# Sheet.net
KiCad netlist of a schematic drawn in Altium Designer
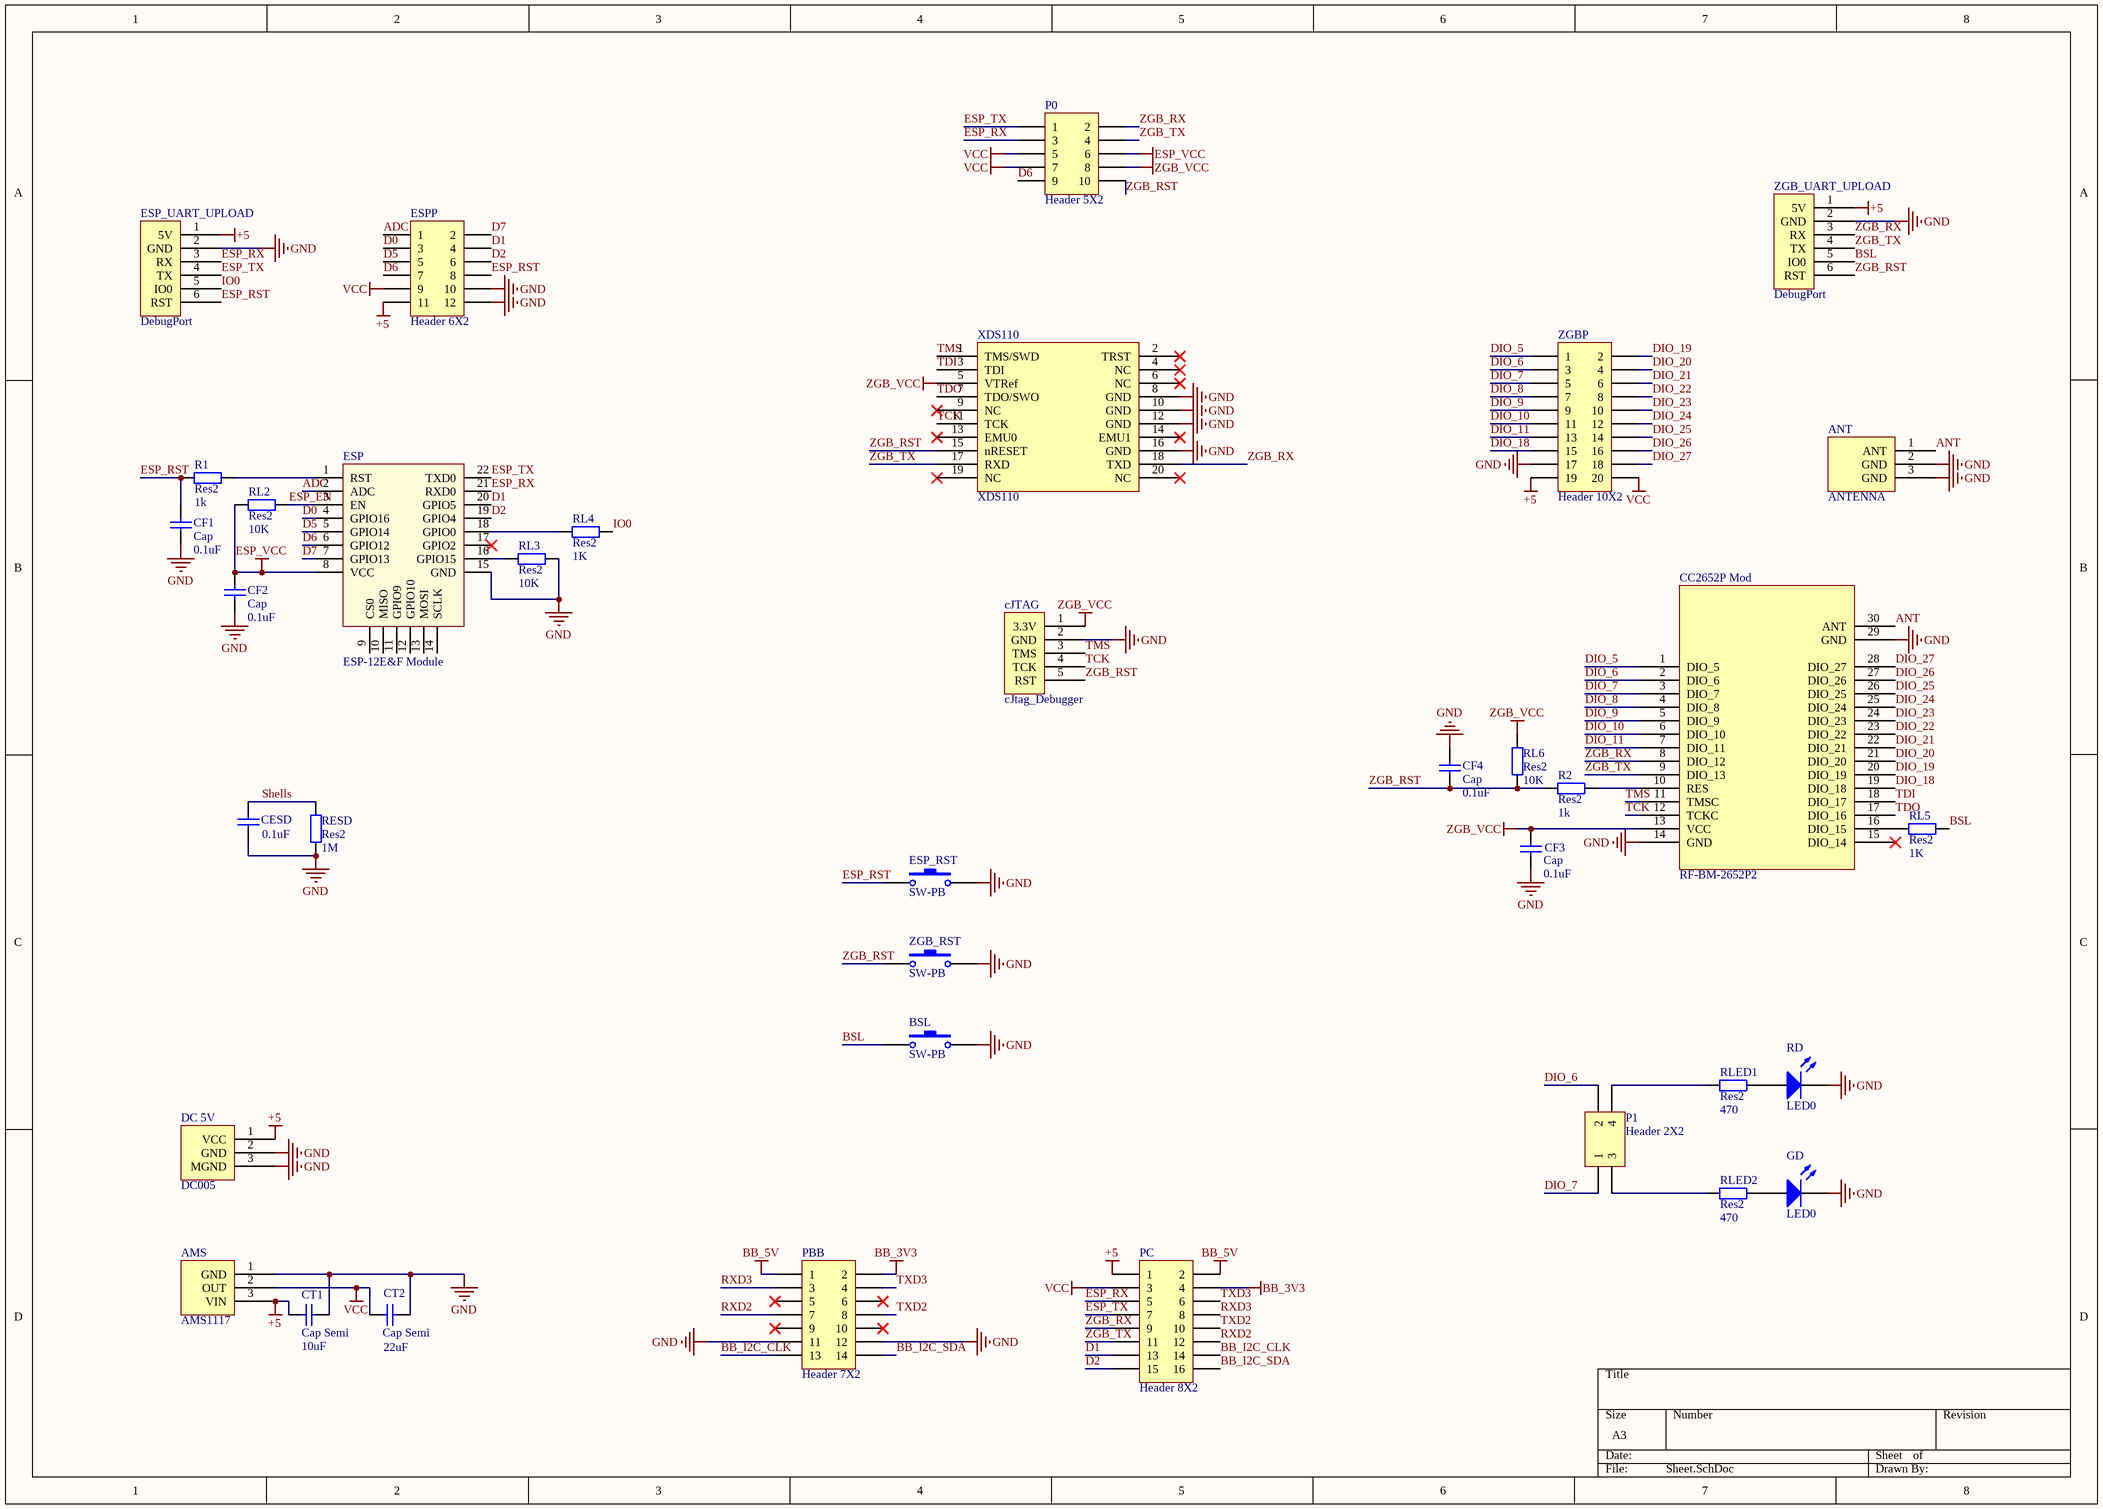
[diagram p0: Sheet.SchDoc]

(export (version "E")
  (design (tool "Eeschema 10.0.6"))
  (components
    (comp (ref "AMS") (value "AMS1117") (footprint "SOT-223-2") (libsource (lib "Schlib2") (part "AMS1117")))
    (comp (ref "ANT") (value "ANTENNA") (footprint "SMA-2") (libsource (lib "我的元件库") (part "ANTENNA")))
    (comp (ref "BSL")
      (value "SW-PB")
      (footprint "TSW SMD-3*6*2.5")
      (description "Switch")
      (fields (field (name "PUBLISHER") "Altium Limited"))
      (libsource (lib "Miscellaneous Devices") (part "SW-PB"))
    )
    (comp (ref "CC2652P Mod")
      (value "RF-BM-2652P2")
      (footprint "RF-BM-2652P2")
      (libsource (lib "我的元件库") (part "RF-BM-2652P2"))
    )
    (comp (ref "CESD")
      (value "0.1uF")
      (footprint "My1206")
      (description "Capacitor")
      (fields (field (name "Comment") "Cap") (field (name "PUBLISHER") "Altium Limited"))
      (libsource (lib "Miscellaneous Devices") (part "Cap"))
    )
    (comp (ref "CF1")
      (value "Cap")
      (footprint "My1206")
      (description "Capacitor")
      (fields (field (name "ALTIUM_VALUE") "0.1uF") (field (name "PUBLISHER") "Altium Limited"))
      (libsource (lib "Miscellaneous Devices") (part "Cap"))
    )
    (comp (ref "CF2")
      (value "Cap")
      (footprint "My1206")
      (description "Capacitor")
      (fields (field (name "ALTIUM_VALUE") "0.1uF") (field (name "PUBLISHER") "Altium Limited"))
      (libsource (lib "Miscellaneous Devices") (part "Cap"))
    )
    (comp (ref "CF3")
      (value "Cap")
      (footprint "My1206")
      (description "Capacitor")
      (fields (field (name "ALTIUM_VALUE") "0.1uF") (field (name "PUBLISHER") "Altium Limited"))
      (libsource (lib "Miscellaneous Devices") (part "Cap"))
    )
    (comp (ref "CF4")
      (value "Cap")
      (footprint "My1206")
      (description "Capacitor")
      (fields (field (name "ALTIUM_VALUE") "0.1uF") (field (name "PUBLISHER") "Altium Limited"))
      (libsource (lib "Miscellaneous Devices") (part "Cap"))
    )
    (comp (ref "cJTAG")
      (value "cJtag_Debugger")
      (footprint "XH2.54-LI-5P")
      (libsource (lib "我的元件库") (part "cJtag_Debugger"))
    )
    (comp (ref "CT1")
      (value "Cap Semi")
      (footprint "My1206")
      (description "Capacitor (Semiconductor SIM Model)")
      (fields (field (name "ALTIUM_VALUE") "10uF") (field (name "PUBLISHER") "Altium Limited"))
      (libsource (lib "Miscellaneous Devices") (part "Cap Semi"))
    )
    (comp (ref "CT2")
      (value "Cap Semi")
      (footprint "My1206")
      (description "Capacitor (Semiconductor SIM Model)")
      (fields (field (name "ALTIUM_VALUE") "22uF") (field (name "PUBLISHER") "Altium Limited"))
      (libsource (lib "Miscellaneous Devices") (part "Cap Semi"))
    )
    (comp (ref "DC 5V") (value "DC005") (footprint "DC-005") (libsource (lib "我的元件库") (part "DC005")))
    (comp (ref "ESP")
      (value "ESP-12E&F Module")
      (footprint "ESP12")
      (libsource (lib "我的元件库") (part "ESP-12E&F Module"))
    )
    (comp (ref "ESPP")
      (value "Header 6X2")
      (footprint "IDC3-6*2")
      (description "Header, 6-Pin, Dual row")
      (fields (field (name "PUBLISHER") "Altium Limited"))
      (libsource (lib "Miscellaneous Connectors") (part "Header 6X2"))
    )
    (comp (ref "ESP_RST")
      (value "SW-PB")
      (footprint "TSW SMD-3*6*2.5")
      (description "Switch")
      (fields (field (name "PUBLISHER") "Altium Limited"))
      (libsource (lib "Miscellaneous Devices") (part "SW-PB"))
    )
    (comp (ref "ESP_UART_UPLOAD")
      (value "DebugPort")
      (footprint "XH2.54-LI-6P")
      (libsource (lib "ESP12_BME280_OLED_IR") (part "DebugPort"))
    )
    (comp (ref "GD")
      (value "LED0")
      (footprint "My1206")
      (description "Typical INFRARED GaAs LED")
      (fields (field (name "PUBLISHER") "Altium Limited"))
      (libsource (lib "Miscellaneous Devices") (part "LED0"))
    )
    (comp (ref "P0")
      (value "Header 5X2")
      (footprint "HDR2X5")
      (description "Header, 5-Pin, Dual row")
      (fields (field (name "PUBLISHER") "Altium Limited"))
      (libsource (lib "Miscellaneous Connectors") (part "Header 5X2"))
    )
    (comp (ref "P1")
      (value "Header 2X2")
      (footprint "HDR2X2")
      (description "Header, 2-Pin, Dual row")
      (fields (field (name "PUBLISHER") "Altium Limited"))
      (libsource (lib "Miscellaneous Connectors") (part "Header 2X2"))
    )
    (comp (ref "PBB")
      (value "Header 7X2")
      (footprint "IDC3-7*2")
      (description "Header, 7-Pin, Dual row")
      (fields (field (name "PUBLISHER") "Altium Limited"))
      (libsource (lib "Miscellaneous Connectors") (part "Header 7X2"))
    )
    (comp (ref "PC")
      (value "Header 8X2")
      (footprint "HDR2X8")
      (description "Header, 8-Pin, Dual row")
      (fields (field (name "PUBLISHER") "Altium Limited"))
      (libsource (lib "Miscellaneous Connectors") (part "Header 8X2"))
    )
    (comp (ref "R1")
      (value "Res2")
      (footprint "My1206")
      (description "Resistor")
      (fields (field (name "ALTIUM_VALUE") "1k") (field (name "PUBLISHER") "Altium Limited"))
      (libsource (lib "Miscellaneous Devices") (part "Res2"))
    )
    (comp (ref "R2")
      (value "Res2")
      (footprint "My1206")
      (description "Resistor")
      (fields (field (name "ALTIUM_VALUE") "1k") (field (name "PUBLISHER") "Altium Limited"))
      (libsource (lib "Miscellaneous Devices") (part "Res2"))
    )
    (comp (ref "RD")
      (value "LED0")
      (footprint "My1206")
      (description "Typical INFRARED GaAs LED")
      (fields (field (name "PUBLISHER") "Altium Limited"))
      (libsource (lib "Miscellaneous Devices") (part "LED0"))
    )
    (comp (ref "RESD")
      (value "Res2")
      (footprint "My1206")
      (description "Resistor")
      (fields (field (name "ALTIUM_VALUE") "1M") (field (name "PUBLISHER") "Altium Limited"))
      (libsource (lib "") (part "Res2_1"))
    )
    (comp (ref "RL2")
      (value "Res2")
      (footprint "My1206")
      (description "Resistor")
      (fields (field (name "ALTIUM_VALUE") "10K") (field (name "PUBLISHER") "Altium Limited"))
      (libsource (lib "Miscellaneous Devices") (part "Res2"))
    )
    (comp (ref "RL3")
      (value "Res2")
      (footprint "My1206")
      (description "Resistor")
      (fields (field (name "ALTIUM_VALUE") "10K") (field (name "PUBLISHER") "Altium Limited"))
      (libsource (lib "Miscellaneous Devices") (part "Res2"))
    )
    (comp (ref "RL4")
      (value "Res2")
      (footprint "My1206")
      (description "Resistor")
      (fields (field (name "ALTIUM_VALUE") "1K") (field (name "PUBLISHER") "Altium Limited"))
      (libsource (lib "Miscellaneous Devices") (part "Res2"))
    )
    (comp (ref "RL5")
      (value "Res2")
      (footprint "My1206")
      (description "Resistor")
      (fields (field (name "ALTIUM_VALUE") "1K") (field (name "PUBLISHER") "Altium Limited"))
      (libsource (lib "Miscellaneous Devices") (part "Res2"))
    )
    (comp (ref "RL6")
      (value "Res2")
      (footprint "My1206")
      (description "Resistor")
      (fields (field (name "ALTIUM_VALUE") "10K") (field (name "PUBLISHER") "Altium Limited"))
      (libsource (lib "") (part "Res2_1"))
    )
    (comp (ref "RLED1")
      (value "Res2")
      (footprint "My1206")
      (description "Resistor")
      (fields (field (name "ALTIUM_VALUE") "470") (field (name "PUBLISHER") "Altium Limited"))
      (libsource (lib "Miscellaneous Devices") (part "Res2"))
    )
    (comp (ref "RLED2")
      (value "Res2")
      (footprint "My1206")
      (description "Resistor")
      (fields (field (name "ALTIUM_VALUE") "470") (field (name "PUBLISHER") "Altium Limited"))
      (libsource (lib "Miscellaneous Devices") (part "Res2"))
    )
    (comp (ref "XDS110") (value "XDS110") (footprint "IDC3-10*2") (libsource (lib "我的元件库") (part "XDS110")))
    (comp (ref "ZGBP")
      (value "Header 10X2")
      (footprint "HDR2X10")
      (description "Header, 10-Pin, Dual row")
      (fields (field (name "PUBLISHER") "Altium Limited"))
      (libsource (lib "Miscellaneous Connectors") (part "Header 10X2"))
    )
    (comp (ref "ZGB_RST")
      (value "SW-PB")
      (footprint "TSW SMD-3*6*2.5")
      (description "Switch")
      (fields (field (name "PUBLISHER") "Altium Limited"))
      (libsource (lib "Miscellaneous Devices") (part "SW-PB"))
    )
    (comp (ref "ZGB_UART_UPLOAD")
      (value "DebugPort")
      (footprint "XH2.54-LI-6P")
      (libsource (lib "ESP12_BME280_OLED_IR") (part "DebugPort"))
    )
  )
  (nets
    (net (code "1") (name "+5") (class "Default")
      (node (ref "AMS") (pin "3") (pinfunction "VIN_3") (pintype "passive"))
      (node (ref "CT1") (pin "1") (pinfunction "1_1") (pintype "passive"))
      (node (ref "DC 5V") (pin "1") (pinfunction "VCC_1") (pintype "passive"))
      (node (ref "ESPP") (pin "11") (pinfunction "11_11") (pintype "passive"))
      (node (ref "ESP_UART_UPLOAD") (pin "1") (pinfunction "5V_1") (pintype "passive"))
      (node (ref "PC") (pin "1") (pinfunction "1_1") (pintype "passive"))
      (node (ref "ZGBP") (pin "19") (pinfunction "19_19") (pintype "passive"))
      (node (ref "ZGB_UART_UPLOAD") (pin "1") (pinfunction "5V_1") (pintype "passive"))
    )
    (net (code "3") (name "/ADC") (class "Default")
      (node (ref "ESP") (pin "2") (pinfunction "ADC_2") (pintype "passive"))
      (node (ref "ESPP") (pin "1") (pinfunction "1_1") (pintype "passive"))
    )
    (net (code "4") (name "/ANT") (class "Default")
      (node (ref "ANT") (pin "1") (pinfunction "ANT_1") (pintype "passive"))
      (node (ref "CC2652P Mod") (pin "30") (pinfunction "ANT_30") (pintype "passive"))
    )
    (net (code "5") (name "/BB_I2C_CLK") (class "Default")
      (node (ref "PBB") (pin "13") (pinfunction "13_13") (pintype "passive"))
      (node (ref "PC") (pin "14") (pinfunction "14_14") (pintype "passive"))
    )
    (net (code "6") (name "/BB_I2C_SDA") (class "Default")
      (node (ref "PBB") (pin "14") (pinfunction "14_14") (pintype "passive"))
      (node (ref "PC") (pin "16") (pinfunction "16_16") (pintype "passive"))
    )
    (net (code "7") (name "/BSL") (class "Default")
      (node (ref "BSL") (pin "1") (pinfunction "1_1") (pintype "passive"))
      (node (ref "RL5") (pin "2") (pinfunction "2_2") (pintype "passive"))
      (node (ref "ZGB_UART_UPLOAD") (pin "5") (pinfunction "IO0_5") (pintype "passive"))
    )
    (net (code "8") (name "/D0") (class "Default")
      (node (ref "ESP") (pin "4") (pinfunction "GPIO16_4") (pintype "passive"))
      (node (ref "ESPP") (pin "3") (pinfunction "3_3") (pintype "passive"))
    )
    (net (code "9") (name "/D1") (class "Default")
      (node (ref "ESP") (pin "20") (pinfunction "GPIO5_20") (pintype "passive"))
      (node (ref "ESPP") (pin "4") (pinfunction "4_4") (pintype "passive"))
      (node (ref "PC") (pin "13") (pinfunction "13_13") (pintype "passive"))
    )
    (net (code "10") (name "/D2") (class "Default")
      (node (ref "ESP") (pin "19") (pinfunction "GPIO4_19") (pintype "passive"))
      (node (ref "ESPP") (pin "6") (pinfunction "6_6") (pintype "passive"))
      (node (ref "PC") (pin "15") (pinfunction "15_15") (pintype "passive"))
    )
    (net (code "11") (name "/D5") (class "Default")
      (node (ref "ESP") (pin "5") (pinfunction "GPIO14_5") (pintype "passive"))
      (node (ref "ESPP") (pin "5") (pinfunction "5_5") (pintype "passive"))
    )
    (net (code "12") (name "/D6") (class "Default")
      (node (ref "ESP") (pin "6") (pinfunction "GPIO12_6") (pintype "passive"))
      (node (ref "ESPP") (pin "7") (pinfunction "7_7") (pintype "passive"))
      (node (ref "P0") (pin "9") (pinfunction "9_9") (pintype "passive"))
    )
    (net (code "13") (name "/D7") (class "Default")
      (node (ref "ESP") (pin "7") (pinfunction "GPIO13_7") (pintype "passive"))
      (node (ref "ESPP") (pin "2") (pinfunction "2_2") (pintype "passive"))
    )
    (net (code "14") (name "/DIO_5") (class "Default")
      (node (ref "CC2652P Mod") (pin "1") (pinfunction "DIO_5_1") (pintype "passive"))
      (node (ref "ZGBP") (pin "1") (pinfunction "1_1") (pintype "passive"))
    )
    (net (code "15") (name "/DIO_6") (class "Default")
      (node (ref "CC2652P Mod") (pin "2") (pinfunction "DIO_6_2") (pintype "passive"))
      (node (ref "P1") (pin "2") (pinfunction "2_2") (pintype "passive"))
      (node (ref "ZGBP") (pin "3") (pinfunction "3_3") (pintype "passive"))
    )
    (net (code "16") (name "/DIO_7") (class "Default")
      (node (ref "CC2652P Mod") (pin "3") (pinfunction "DIO_7_3") (pintype "passive"))
      (node (ref "P1") (pin "1") (pinfunction "1_1") (pintype "passive"))
      (node (ref "ZGBP") (pin "5") (pinfunction "5_5") (pintype "passive"))
    )
    (net (code "17") (name "/DIO_8") (class "Default")
      (node (ref "CC2652P Mod") (pin "4") (pinfunction "DIO_8_4") (pintype "passive"))
      (node (ref "ZGBP") (pin "7") (pinfunction "7_7") (pintype "passive"))
    )
    (net (code "18") (name "/DIO_9") (class "Default")
      (node (ref "CC2652P Mod") (pin "5") (pinfunction "DIO_9_5") (pintype "passive"))
      (node (ref "ZGBP") (pin "9") (pinfunction "9_9") (pintype "passive"))
    )
    (net (code "19") (name "/DIO_10") (class "Default")
      (node (ref "CC2652P Mod") (pin "6") (pinfunction "DIO_10_6") (pintype "passive"))
      (node (ref "ZGBP") (pin "11") (pinfunction "11_11") (pintype "passive"))
    )
    (net (code "20") (name "/DIO_11") (class "Default")
      (node (ref "CC2652P Mod") (pin "7") (pinfunction "DIO_11_7") (pintype "passive"))
      (node (ref "ZGBP") (pin "13") (pinfunction "13_13") (pintype "passive"))
    )
    (net (code "21") (name "/DIO_18") (class "Default")
      (node (ref "CC2652P Mod") (pin "19") (pinfunction "DIO_18_19") (pintype "passive"))
      (node (ref "ZGBP") (pin "15") (pinfunction "15_15") (pintype "passive"))
    )
    (net (code "22") (name "/DIO_19") (class "Default")
      (node (ref "CC2652P Mod") (pin "20") (pinfunction "DIO_19_20") (pintype "passive"))
      (node (ref "ZGBP") (pin "2") (pinfunction "2_2") (pintype "passive"))
    )
    (net (code "23") (name "/DIO_20") (class "Default")
      (node (ref "CC2652P Mod") (pin "21") (pinfunction "DIO_20_21") (pintype "passive"))
      (node (ref "ZGBP") (pin "4") (pinfunction "4_4") (pintype "passive"))
    )
    (net (code "24") (name "/DIO_21") (class "Default")
      (node (ref "CC2652P Mod") (pin "22") (pinfunction "DIO_21_22") (pintype "passive"))
      (node (ref "ZGBP") (pin "6") (pinfunction "6_6") (pintype "passive"))
    )
    (net (code "25") (name "/DIO_22") (class "Default")
      (node (ref "CC2652P Mod") (pin "23") (pinfunction "DIO_22_23") (pintype "passive"))
      (node (ref "ZGBP") (pin "8") (pinfunction "8_8") (pintype "passive"))
    )
    (net (code "26") (name "/DIO_23") (class "Default")
      (node (ref "CC2652P Mod") (pin "24") (pinfunction "DIO_23_24") (pintype "passive"))
      (node (ref "ZGBP") (pin "10") (pinfunction "10_10") (pintype "passive"))
    )
    (net (code "27") (name "/DIO_24") (class "Default")
      (node (ref "CC2652P Mod") (pin "25") (pinfunction "DIO_24_25") (pintype "passive"))
      (node (ref "ZGBP") (pin "12") (pinfunction "12_12") (pintype "passive"))
    )
    (net (code "28") (name "/DIO_25") (class "Default")
      (node (ref "CC2652P Mod") (pin "26") (pinfunction "DIO_25_26") (pintype "passive"))
      (node (ref "ZGBP") (pin "14") (pinfunction "14_14") (pintype "passive"))
    )
    (net (code "29") (name "/DIO_26") (class "Default")
      (node (ref "CC2652P Mod") (pin "27") (pinfunction "DIO_26_27") (pintype "passive"))
      (node (ref "ZGBP") (pin "16") (pinfunction "16_16") (pintype "passive"))
    )
    (net (code "30") (name "/DIO_27") (class "Default")
      (node (ref "CC2652P Mod") (pin "28") (pinfunction "DIO_27_28") (pintype "passive"))
      (node (ref "ZGBP") (pin "18") (pinfunction "18_18") (pintype "passive"))
    )
    (net (code "31") (name "/ESP_EN") (class "Default")
      (node (ref "ESP") (pin "3") (pinfunction "EN_3") (pintype "passive"))
      (node (ref "RL2") (pin "2") (pinfunction "2_2") (pintype "passive"))
    )
    (net (code "32") (name "/ESP_RST") (class "Default")
      (node (ref "CF1") (pin "2") (pinfunction "2_2") (pintype "passive"))
      (node (ref "ESPP") (pin "8") (pinfunction "8_8") (pintype "passive"))
      (node (ref "ESP_RST") (pin "1") (pinfunction "1_1") (pintype "passive"))
      (node (ref "ESP_UART_UPLOAD") (pin "6") (pinfunction "RST_6") (pintype "passive"))
      (node (ref "R1") (pin "1") (pinfunction "1_1") (pintype "passive"))
    )
    (net (code "33") (name "/ESP_RX") (class "Default")
      (node (ref "ESP") (pin "21") (pinfunction "RXD0_21") (pintype "passive"))
      (node (ref "ESP_UART_UPLOAD") (pin "3") (pinfunction "RX_3") (pintype "passive"))
      (node (ref "P0") (pin "3") (pinfunction "3_3") (pintype "passive"))
      (node (ref "PC") (pin "5") (pinfunction "5_5") (pintype "passive"))
    )
    (net (code "34") (name "/ESP_TX") (class "Default")
      (node (ref "ESP") (pin "22") (pinfunction "TXD0_22") (pintype "passive"))
      (node (ref "ESP_UART_UPLOAD") (pin "4") (pinfunction "TX_4") (pintype "passive"))
      (node (ref "P0") (pin "1") (pinfunction "1_1") (pintype "passive"))
      (node (ref "PC") (pin "7") (pinfunction "7_7") (pintype "passive"))
    )
    (net (code "35") (name "/IO0") (class "Default")
      (node (ref "ESP_UART_UPLOAD") (pin "5") (pinfunction "IO0_5") (pintype "passive"))
      (node (ref "RL4") (pin "2") (pinfunction "2_2") (pintype "passive"))
    )
    (net (code "36") (name "/RXD2") (class "Default")
      (node (ref "PBB") (pin "7") (pinfunction "7_7") (pintype "passive"))
      (node (ref "PC") (pin "12") (pinfunction "12_12") (pintype "passive"))
    )
    (net (code "37") (name "/RXD3") (class "Default")
      (node (ref "PBB") (pin "3") (pinfunction "3_3") (pintype "passive"))
      (node (ref "PC") (pin "8") (pinfunction "8_8") (pintype "passive"))
    )
    (net (code "38") (name "/Shells") (class "Default")
      (node (ref "CESD") (pin "2") (pinfunction "2_2") (pintype "passive"))
      (node (ref "RESD") (pin "2") (pinfunction "2_2") (pintype "passive"))
    )
    (net (code "39") (name "/TCK") (class "Default")
      (node (ref "CC2652P Mod") (pin "12") (pinfunction "TCKC_12") (pintype "passive"))
      (node (ref "XDS110") (pin "11") (pinfunction "TCK_11") (pintype "passive"))
      (node (ref "cJTAG") (pin "4") (pinfunction "TCK_4") (pintype "passive"))
    )
    (net (code "40") (name "/TDI") (class "Default")
      (node (ref "CC2652P Mod") (pin "18") (pinfunction "DIO_17_18") (pintype "passive"))
      (node (ref "XDS110") (pin "3") (pinfunction "TDI_3") (pintype "passive"))
    )
    (net (code "41") (name "/TDO") (class "Default")
      (node (ref "CC2652P Mod") (pin "17") (pinfunction "DIO_16_17") (pintype "passive"))
      (node (ref "XDS110") (pin "7") (pinfunction "TDO/SWO_7") (pintype "passive"))
    )
    (net (code "42") (name "/TMS") (class "Default")
      (node (ref "CC2652P Mod") (pin "11") (pinfunction "TMSC_11") (pintype "passive"))
      (node (ref "XDS110") (pin "1") (pinfunction "TMS/SWD_1") (pintype "passive"))
      (node (ref "cJTAG") (pin "3") (pinfunction "TMS_3") (pintype "passive"))
    )
    (net (code "43") (name "/TXD2") (class "Default")
      (node (ref "PBB") (pin "8") (pinfunction "8_8") (pintype "passive"))
      (node (ref "PC") (pin "10") (pinfunction "10_10") (pintype "passive"))
    )
    (net (code "44") (name "/TXD3") (class "Default")
      (node (ref "PBB") (pin "4") (pinfunction "4_4") (pintype "passive"))
      (node (ref "PC") (pin "6") (pinfunction "6_6") (pintype "passive"))
    )
    (net (code "45") (name "/ZGB_RST") (class "Default")
      (node (ref "CF4") (pin "2") (pinfunction "2_2") (pintype "passive"))
      (node (ref "P0") (pin "10") (pinfunction "10_10") (pintype "passive"))
      (node (ref "R2") (pin "1") (pinfunction "1_1") (pintype "passive"))
      (node (ref "RL6") (pin "1") (pinfunction "1_1") (pintype "passive"))
      (node (ref "XDS110") (pin "15") (pinfunction "nRESET_15") (pintype "passive"))
      (node (ref "ZGB_RST") (pin "1") (pinfunction "1_1") (pintype "passive"))
      (node (ref "ZGB_UART_UPLOAD") (pin "6") (pinfunction "RST_6") (pintype "passive"))
      (node (ref "cJTAG") (pin "5") (pinfunction "RST_5") (pintype "passive"))
    )
    (net (code "46") (name "/ZGB_RX") (class "Default")
      (node (ref "CC2652P Mod") (pin "8") (pinfunction "DIO_12_8") (pintype "passive"))
      (node (ref "P0") (pin "2") (pinfunction "2_2") (pintype "passive"))
      (node (ref "PC") (pin "9") (pinfunction "9_9") (pintype "passive"))
      (node (ref "XDS110") (pin "18") (pinfunction "TXD_18") (pintype "passive"))
      (node (ref "ZGB_UART_UPLOAD") (pin "3") (pinfunction "RX_3") (pintype "passive"))
    )
    (net (code "47") (name "/ZGB_TX") (class "Default")
      (node (ref "CC2652P Mod") (pin "9") (pinfunction "DIO_13_9") (pintype "passive"))
      (node (ref "P0") (pin "4") (pinfunction "4_4") (pintype "passive"))
      (node (ref "PC") (pin "11") (pinfunction "11_11") (pintype "passive"))
      (node (ref "XDS110") (pin "17") (pinfunction "RXD_17") (pintype "passive"))
      (node (ref "ZGB_UART_UPLOAD") (pin "4") (pinfunction "TX_4") (pintype "passive"))
    )
    (net (code "48") (name "BB_3V3") (class "Default")
      (node (ref "PBB") (pin "2") (pinfunction "2_2") (pintype "passive"))
      (node (ref "PC") (pin "4") (pinfunction "4_4") (pintype "passive"))
    )
    (net (code "49") (name "BB_5V") (class "Default")
      (node (ref "PBB") (pin "1") (pinfunction "1_1") (pintype "passive"))
      (node (ref "PC") (pin "2") (pinfunction "2_2") (pintype "passive"))
    )
    (net (code "50") (name "ESP_VCC") (class "Default")
      (node (ref "CF2") (pin "2") (pinfunction "2_2") (pintype "passive"))
      (node (ref "ESP") (pin "8") (pinfunction "VCC_8") (pintype "passive"))
      (node (ref "P0") (pin "6") (pinfunction "6_6") (pintype "passive"))
      (node (ref "RL2") (pin "1") (pinfunction "1_1") (pintype "passive"))
    )
    (net (code "51") (name "GND") (class "Default")
      (node (ref "AMS") (pin "1") (pinfunction "GND_1") (pintype "passive"))
      (node (ref "ANT") (pin "2") (pinfunction "GND_2") (pintype "passive"))
      (node (ref "ANT") (pin "3") (pinfunction "GND_3") (pintype "passive"))
      (node (ref "BSL") (pin "2") (pinfunction "2_2") (pintype "passive"))
      (node (ref "CC2652P Mod") (pin "14") (pinfunction "GND_14") (pintype "passive"))
      (node (ref "CC2652P Mod") (pin "29") (pinfunction "GND_29") (pintype "passive"))
      (node (ref "CESD") (pin "1") (pinfunction "1_1") (pintype "passive"))
      (node (ref "CF1") (pin "1") (pinfunction "1_1") (pintype "passive"))
      (node (ref "CF2") (pin "1") (pinfunction "1_1") (pintype "passive"))
      (node (ref "CF3") (pin "1") (pinfunction "1_1") (pintype "passive"))
      (node (ref "CF4") (pin "1") (pinfunction "1_1") (pintype "passive"))
      (node (ref "CT1") (pin "2") (pinfunction "2_2") (pintype "passive"))
      (node (ref "CT2") (pin "2") (pinfunction "2_2") (pintype "passive"))
      (node (ref "DC 5V") (pin "2") (pinfunction "GND_2") (pintype "passive"))
      (node (ref "DC 5V") (pin "3") (pinfunction "MGND_3") (pintype "passive"))
      (node (ref "ESP") (pin "15") (pinfunction "GND_15") (pintype "passive"))
      (node (ref "ESPP") (pin "10") (pinfunction "10_10") (pintype "passive"))
      (node (ref "ESPP") (pin "12") (pinfunction "12_12") (pintype "passive"))
      (node (ref "ESP_RST") (pin "2") (pinfunction "2_2") (pintype "passive"))
      (node (ref "ESP_UART_UPLOAD") (pin "2") (pinfunction "GND_2") (pintype "passive"))
      (node (ref "GD") (pin "2") (pinfunction "K_2") (pintype "passive"))
      (node (ref "PBB") (pin "11") (pinfunction "11_11") (pintype "passive"))
      (node (ref "PBB") (pin "12") (pinfunction "12_12") (pintype "passive"))
      (node (ref "RD") (pin "2") (pinfunction "K_2") (pintype "passive"))
      (node (ref "RESD") (pin "1") (pinfunction "1_1") (pintype "passive"))
      (node (ref "RL3") (pin "2") (pinfunction "2_2") (pintype "passive"))
      (node (ref "XDS110") (pin "10") (pinfunction "GND_10") (pintype "passive"))
      (node (ref "XDS110") (pin "12") (pinfunction "GND_12") (pintype "passive"))
      (node (ref "XDS110") (pin "16") (pinfunction "GND_16") (pintype "passive"))
      (node (ref "XDS110") (pin "8") (pinfunction "GND_8") (pintype "passive"))
      (node (ref "ZGBP") (pin "17") (pinfunction "17_17") (pintype "passive"))
      (node (ref "ZGB_RST") (pin "2") (pinfunction "2_2") (pintype "passive"))
      (node (ref "ZGB_UART_UPLOAD") (pin "2") (pinfunction "GND_2") (pintype "passive"))
      (node (ref "cJTAG") (pin "2") (pinfunction "GND_2") (pintype "passive"))
    )
    (net (code "52") (name "Net-(CC2652P Mod-DIO_15)") (class "Default")
      (node (ref "CC2652P Mod") (pin "16") (pinfunction "DIO_15_16") (pintype "passive"))
      (node (ref "RL5") (pin "1") (pinfunction "1_1") (pintype "passive"))
    )
    (net (code "53") (name "Net-(CC2652P Mod-RES)") (class "Default")
      (node (ref "CC2652P Mod") (pin "10") (pinfunction "RES_10") (pintype "passive"))
      (node (ref "R2") (pin "2") (pinfunction "2_2") (pintype "passive"))
    )
    (net (code "54") (name "Net-(ESP-GPIO0)") (class "Default")
      (node (ref "ESP") (pin "18") (pinfunction "GPIO0_18") (pintype "passive"))
      (node (ref "RL4") (pin "1") (pinfunction "1_1") (pintype "passive"))
    )
    (net (code "55") (name "Net-(ESP-GPIO15)") (class "Default")
      (node (ref "ESP") (pin "16") (pinfunction "GPIO15_16") (pintype "passive"))
      (node (ref "RL3") (pin "1") (pinfunction "1_1") (pintype "passive"))
    )
    (net (code "56") (name "Net-(ESP-RST)") (class "Default")
      (node (ref "ESP") (pin "1") (pinfunction "RST_1") (pintype "passive"))
      (node (ref "R1") (pin "2") (pinfunction "2_2") (pintype "passive"))
    )
    (net (code "57") (name "Net-(GD-A)") (class "Default")
      (node (ref "GD") (pin "1") (pinfunction "A_1") (pintype "passive"))
      (node (ref "RLED2") (pin "2") (pinfunction "2_2") (pintype "passive"))
    )
    (net (code "58") (name "Net-(P1-Pad3)") (class "Default")
      (node (ref "P1") (pin "3") (pinfunction "3_3") (pintype "passive"))
      (node (ref "RLED2") (pin "1") (pinfunction "1_1") (pintype "passive"))
    )
    (net (code "59") (name "Net-(P1-Pad4)") (class "Default")
      (node (ref "P1") (pin "4") (pinfunction "4_4") (pintype "passive"))
      (node (ref "RLED1") (pin "1") (pinfunction "1_1") (pintype "passive"))
    )
    (net (code "60") (name "Net-(RD-A)") (class "Default")
      (node (ref "RD") (pin "1") (pinfunction "A_1") (pintype "passive"))
      (node (ref "RLED1") (pin "2") (pinfunction "2_2") (pintype "passive"))
    )
    (net (code "61") (name "VCC") (class "Default")
      (node (ref "AMS") (pin "2") (pinfunction "OUT_2") (pintype "passive"))
      (node (ref "CT2") (pin "1") (pinfunction "1_1") (pintype "passive"))
      (node (ref "ESPP") (pin "9") (pinfunction "9_9") (pintype "passive"))
      (node (ref "P0") (pin "5") (pinfunction "5_5") (pintype "passive"))
      (node (ref "P0") (pin "7") (pinfunction "7_7") (pintype "passive"))
      (node (ref "PC") (pin "3") (pinfunction "3_3") (pintype "passive"))
      (node (ref "ZGBP") (pin "20") (pinfunction "20_20") (pintype "passive"))
    )
    (net (code "62") (name "ZGB_VCC") (class "Default")
      (node (ref "CC2652P Mod") (pin "13") (pinfunction "VCC_13") (pintype "passive"))
      (node (ref "CF3") (pin "2") (pinfunction "2_2") (pintype "passive"))
      (node (ref "P0") (pin "8") (pinfunction "8_8") (pintype "passive"))
      (node (ref "RL6") (pin "2") (pinfunction "2_2") (pintype "passive"))
      (node (ref "XDS110") (pin "5") (pinfunction "VTRef_5") (pintype "passive"))
      (node (ref "cJTAG") (pin "1") (pinfunction "3.3V_1") (pintype "passive"))
    )
    (net (code "63") (name "unconnected-(CC2652P Mod-DIO_14-Pad15)") (class "Default")
      (node (ref "CC2652P Mod") (pin "15") (pinfunction "DIO_14_15") (pintype "passive+no_connect"))
    )
    (net (code "64") (name "unconnected-(ESP-CS0-Pad9)") (class "Default")
      (node (ref "ESP") (pin "9") (pinfunction "CS0_9") (pintype "passive"))
    )
    (net (code "65") (name "unconnected-(ESP-GPIO2-Pad17)") (class "Default")
      (node (ref "ESP") (pin "17") (pinfunction "GPIO2_17") (pintype "passive+no_connect"))
    )
    (net (code "66") (name "unconnected-(ESP-GPIO9-Pad11)") (class "Default")
      (node (ref "ESP") (pin "11") (pinfunction "GPIO9_11") (pintype "passive"))
    )
    (net (code "67") (name "unconnected-(ESP-GPIO10-Pad12)") (class "Default")
      (node (ref "ESP") (pin "12") (pinfunction "GPIO10_12") (pintype "passive"))
    )
    (net (code "68") (name "unconnected-(ESP-MISO-Pad10)") (class "Default")
      (node (ref "ESP") (pin "10") (pinfunction "MISO_10") (pintype "passive"))
    )
    (net (code "69") (name "unconnected-(ESP-MOSI-Pad13)") (class "Default")
      (node (ref "ESP") (pin "13") (pinfunction "MOSI_13") (pintype "passive"))
    )
    (net (code "70") (name "unconnected-(ESP-SCLK-Pad14)") (class "Default")
      (node (ref "ESP") (pin "14") (pinfunction "SCLK_14") (pintype "passive"))
    )
    (net (code "71") (name "unconnected-(PBB-Pad5)") (class "Default")
      (node (ref "PBB") (pin "5") (pinfunction "5_5") (pintype "passive+no_connect"))
    )
    (net (code "72") (name "unconnected-(PBB-Pad6)") (class "Default")
      (node (ref "PBB") (pin "6") (pinfunction "6_6") (pintype "passive+no_connect"))
    )
    (net (code "73") (name "unconnected-(PBB-Pad9)") (class "Default")
      (node (ref "PBB") (pin "9") (pinfunction "9_9") (pintype "passive+no_connect"))
    )
    (net (code "74") (name "unconnected-(PBB-Pad10)") (class "Default")
      (node (ref "PBB") (pin "10") (pinfunction "10_10") (pintype "passive+no_connect"))
    )
    (net (code "75") (name "unconnected-(XDS110-EMU0-Pad13)") (class "Default")
      (node (ref "XDS110") (pin "13") (pinfunction "EMU0_13") (pintype "passive+no_connect"))
    )
    (net (code "76") (name "unconnected-(XDS110-EMU1-Pad14)") (class "Default")
      (node (ref "XDS110") (pin "14") (pinfunction "EMU1_14") (pintype "passive+no_connect"))
    )
    (net (code "77") (name "unconnected-(XDS110-NC-Pad4)") (class "Default")
      (node (ref "XDS110") (pin "4") (pinfunction "NC_4") (pintype "passive+no_connect"))
    )
    (net (code "78") (name "unconnected-(XDS110-NC-Pad6)") (class "Default")
      (node (ref "XDS110") (pin "6") (pinfunction "NC_6") (pintype "passive+no_connect"))
    )
    (net (code "79") (name "unconnected-(XDS110-NC-Pad9)") (class "Default")
      (node (ref "XDS110") (pin "9") (pinfunction "NC_9") (pintype "passive+no_connect"))
    )
    (net (code "80") (name "unconnected-(XDS110-NC-Pad19)") (class "Default")
      (node (ref "XDS110") (pin "19") (pinfunction "NC_19") (pintype "passive+no_connect"))
    )
    (net (code "81") (name "unconnected-(XDS110-NC-Pad20)") (class "Default")
      (node (ref "XDS110") (pin "20") (pinfunction "NC_20") (pintype "passive+no_connect"))
    )
    (net (code "82") (name "unconnected-(XDS110-TRST-Pad2)") (class "Default")
      (node (ref "XDS110") (pin "2") (pinfunction "TRST_2") (pintype "passive+no_connect"))
    )
  )
)
